# mattduino_mega_nano.net
KiCad netlist of a schematic drawn in EAGLE
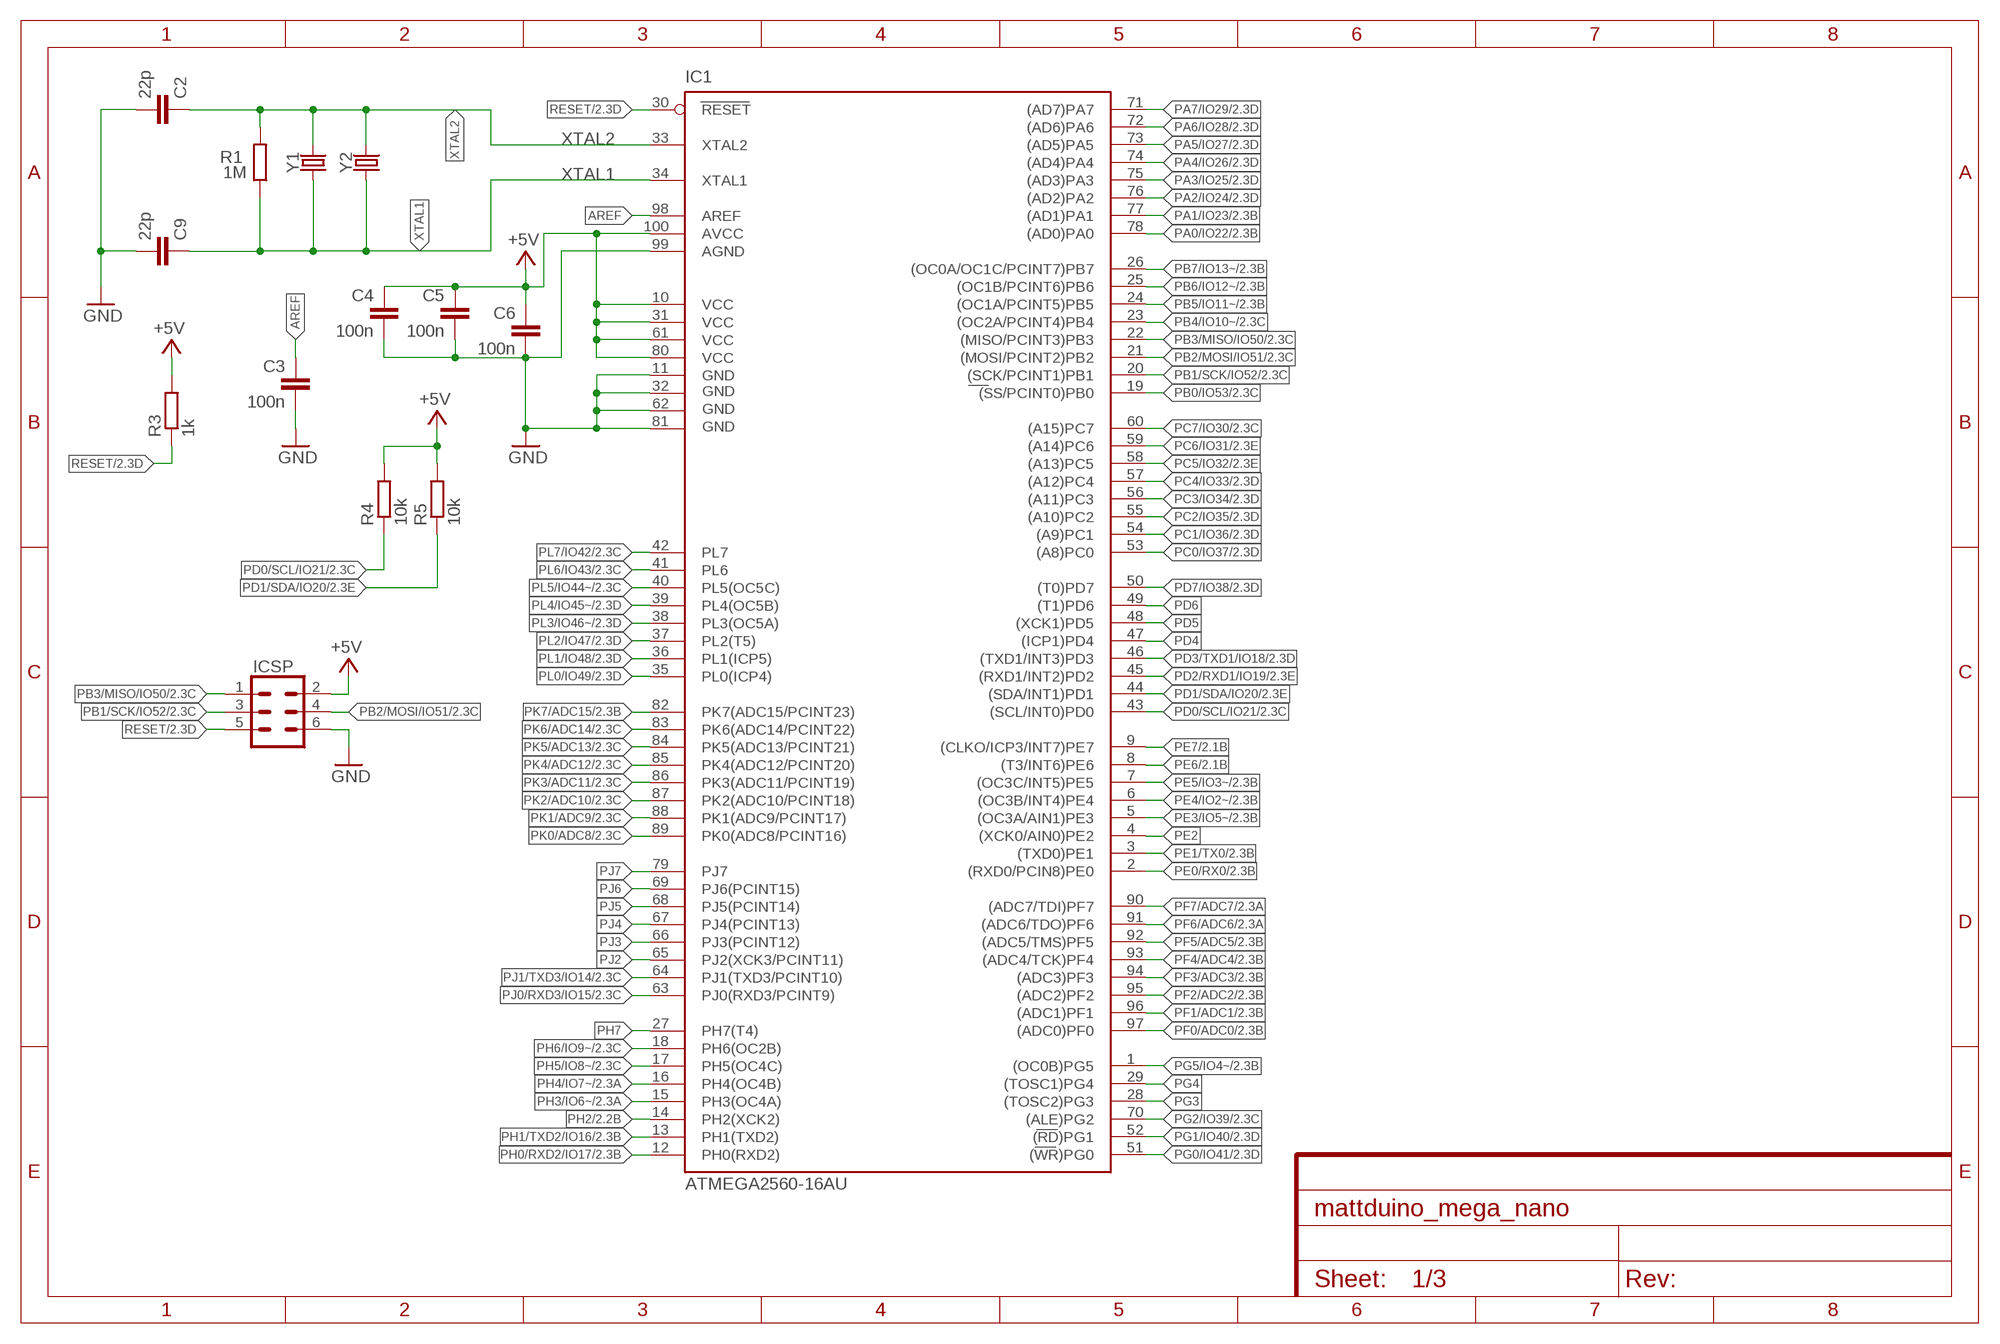
[diagram p0: schematic, sheet 1]
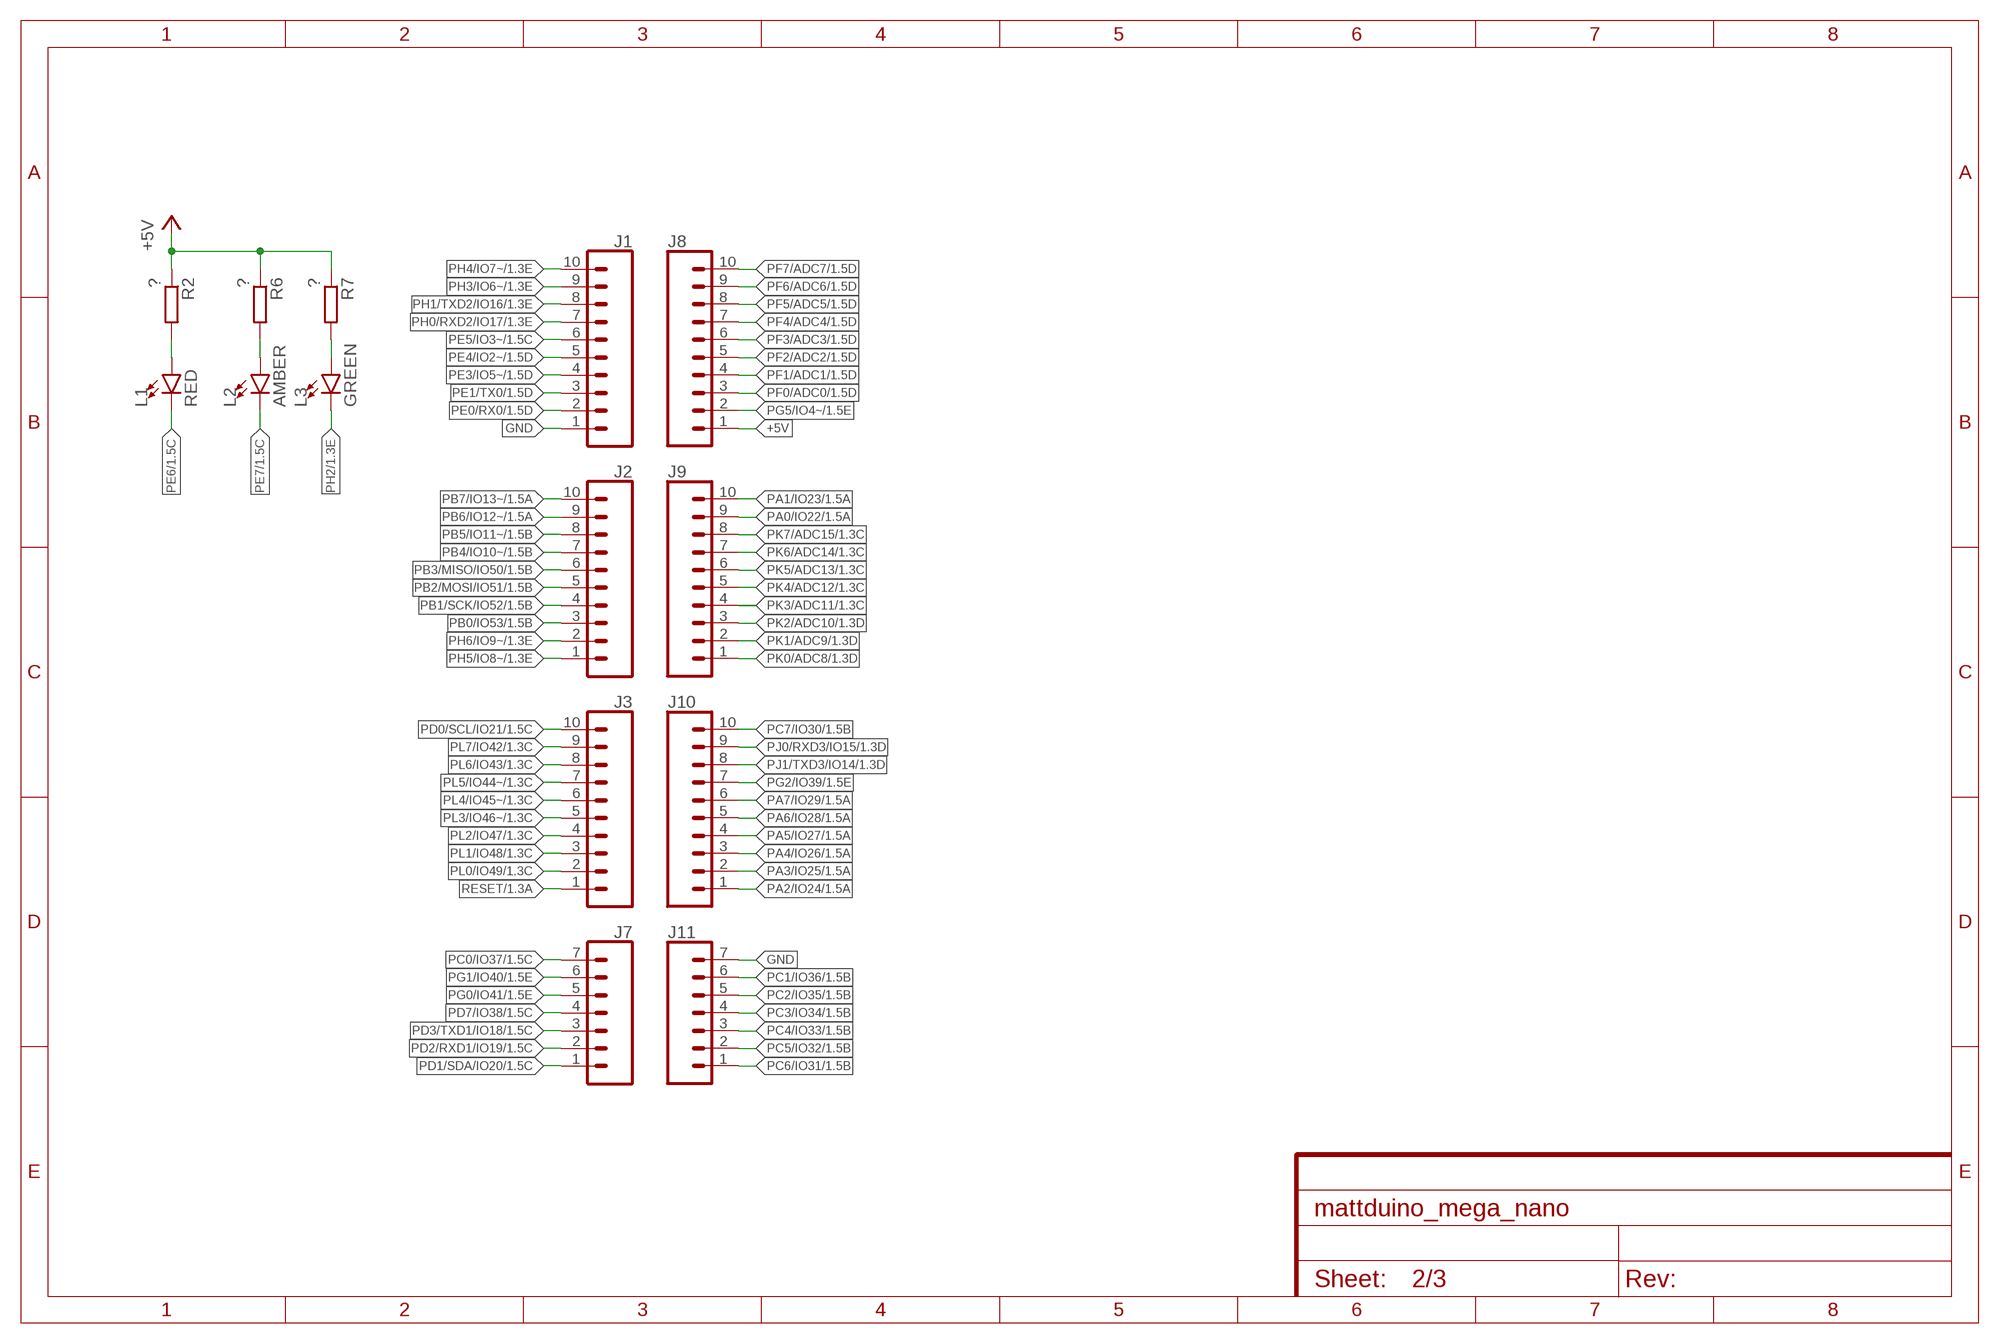
[diagram p1: schematic, sheet 2]
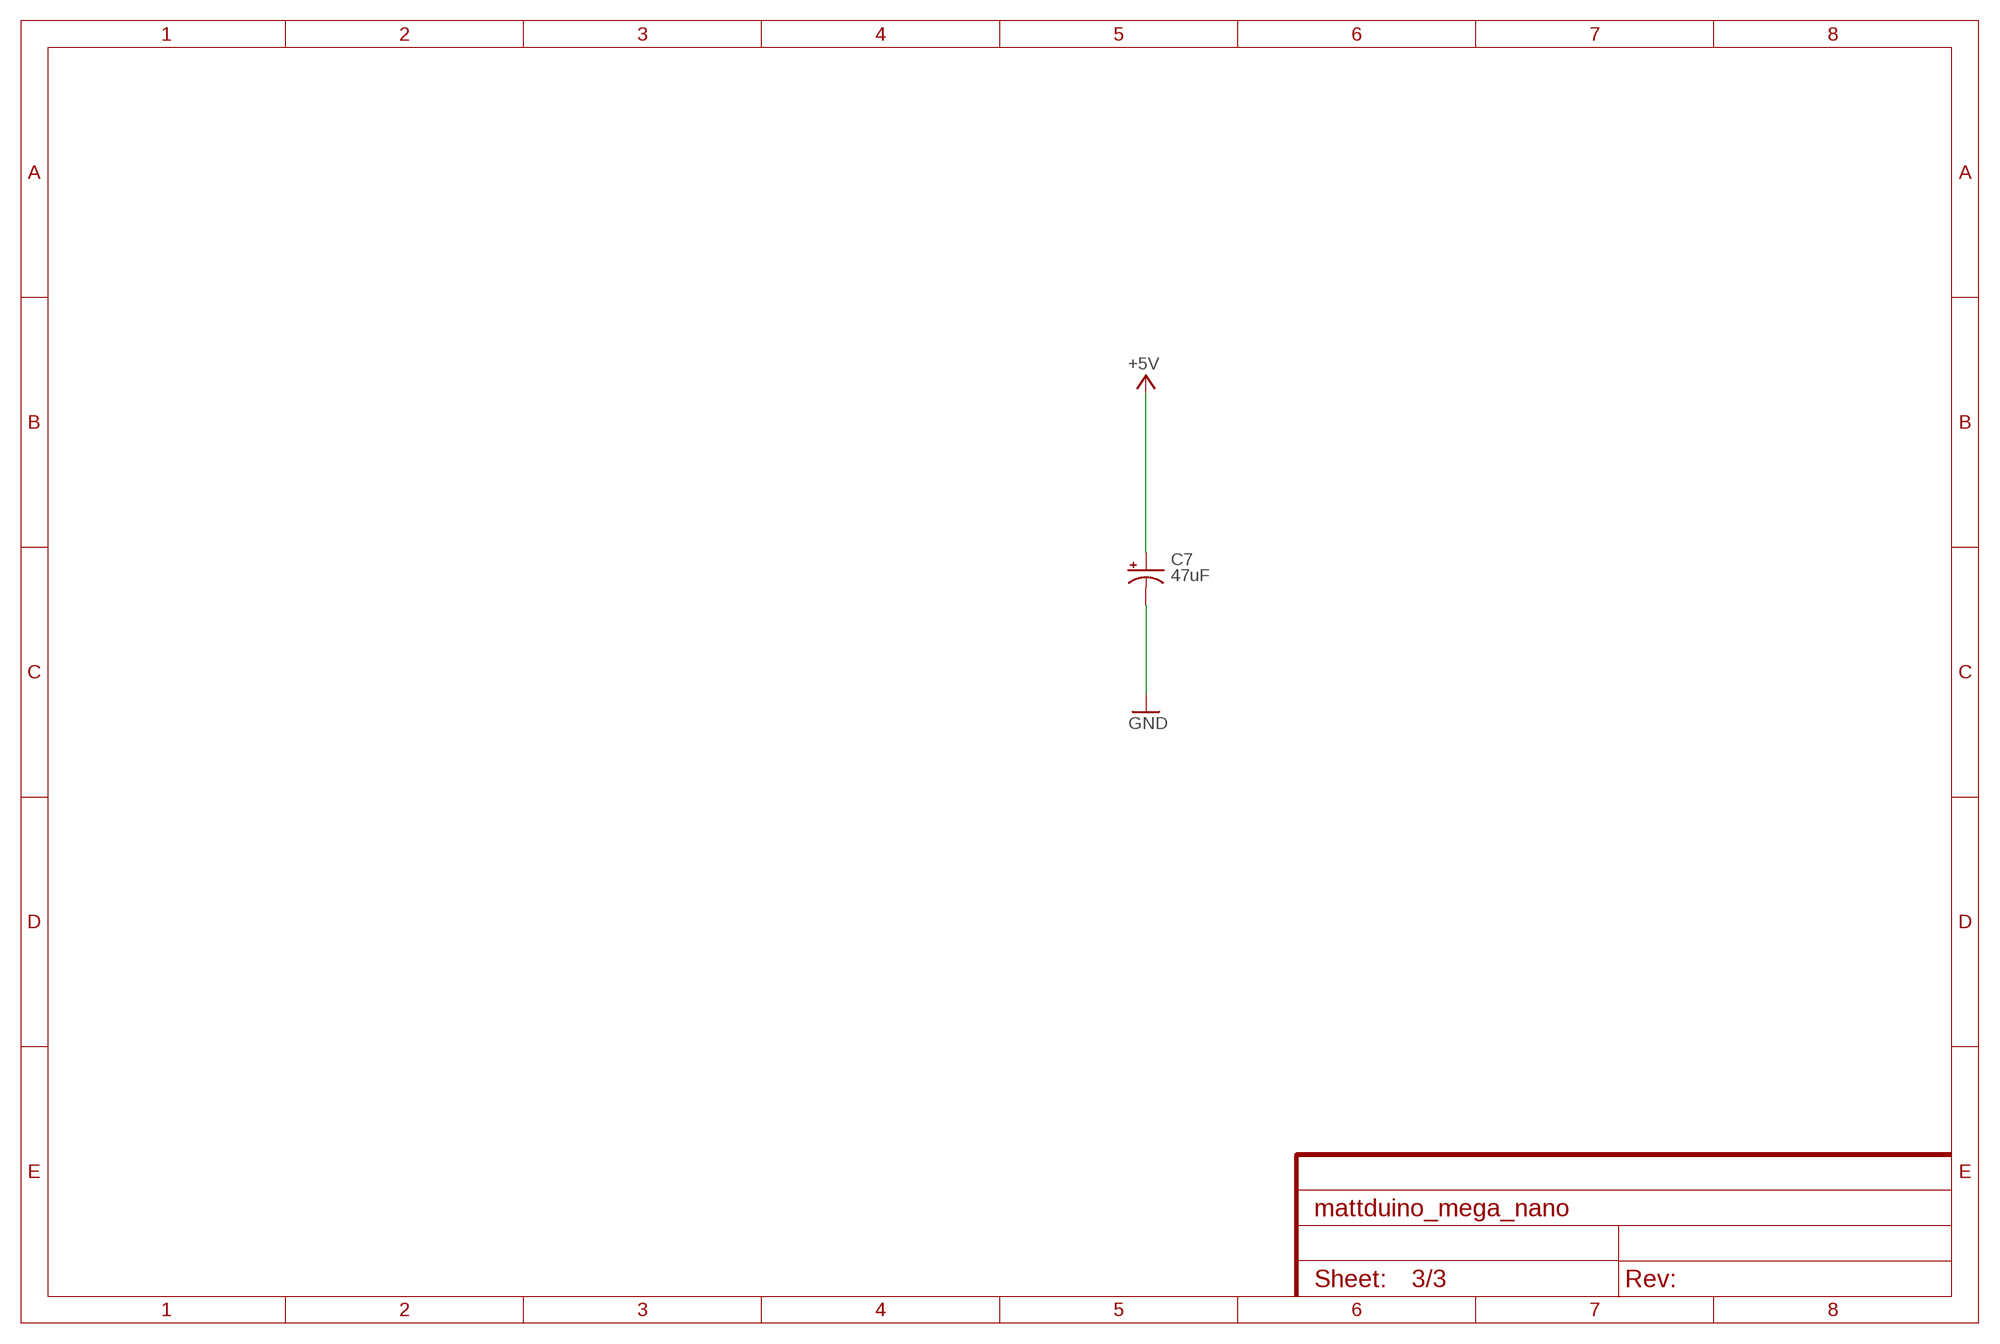
[diagram p2: schematic, sheet 3]

(export (version "E")
  (design (tool "Eeschema 10.0.6"))
  (components
    (comp (ref "J1")
      (value "CONN_10LOCK")
      (footprint "eagle-import:1X10_LOCK")
      (libsource (lib "eagle-import") (part "CONN_10LOCK"))
    )
    (comp (ref "J2")
      (value "CONN_10LOCK")
      (footprint "eagle-import:1X10_LOCK")
      (libsource (lib "eagle-import") (part "CONN_10LOCK"))
    )
    (comp (ref "J3")
      (value "CONN_10LOCK")
      (footprint "eagle-import:1X10_LOCK")
      (libsource (lib "eagle-import") (part "CONN_10LOCK"))
    )
    (comp (ref "J7")
      (value "CONN_07LOCK")
      (footprint "eagle-import:1X07_LOCK")
      (libsource (lib "eagle-import") (part "CONN_07LOCK"))
    )
    (comp (ref "J8")
      (value "CONN_10LOCK")
      (footprint "eagle-import:1X10_LOCK")
      (libsource (lib "eagle-import") (part "CONN_10LOCK"))
    )
    (comp (ref "J9")
      (value "CONN_10LOCK")
      (footprint "eagle-import:1X10_LOCK")
      (libsource (lib "eagle-import") (part "CONN_10LOCK"))
    )
    (comp (ref "J10")
      (value "CONN_10LOCK")
      (footprint "eagle-import:1X10_LOCK")
      (libsource (lib "eagle-import") (part "CONN_10LOCK"))
    )
    (comp (ref "J11")
      (value "CONN_07LOCK")
      (footprint "eagle-import:1X07_LOCK")
      (libsource (lib "eagle-import") (part "CONN_07LOCK"))
    )
    (comp (ref "L1")
      (value "RED")
      (footprint "eagle-import:LED-0603")
      (libsource (lib "eagle-import") (part "LED0603"))
    )
    (comp (ref "L2")
      (value "AMBER")
      (footprint "eagle-import:LED-0603")
      (libsource (lib "eagle-import") (part "LED0603"))
    )
    (comp (ref "L3")
      (value "GREEN")
      (footprint "eagle-import:LED-0603")
      (libsource (lib "eagle-import") (part "LED0603"))
    )
    (comp (ref "R2")
      (value "?")
      (footprint "eagle-import:R0603")
      (libsource (lib "eagle-import") (part "R-EU_R0603"))
    )
    (comp (ref "R6")
      (value "?")
      (footprint "eagle-import:R0603")
      (libsource (lib "eagle-import") (part "R-EU_R0603"))
    )
    (comp (ref "R7")
      (value "?")
      (footprint "eagle-import:R0603")
      (libsource (lib "eagle-import") (part "R-EU_R0603"))
    )
    (comp (ref "C7")
      (value "47uF")
      (footprint "eagle-import:PANASONIC_D")
      (libsource (lib "eagle-import") (part "47UF-POLAR-PANASONIC_D-35V-20%"))
    )
    (comp (ref "C2")
      (value "22p")
      (footprint "eagle-import:C0603")
      (libsource (lib "eagle-import") (part "C-EUC0603"))
    )
    (comp (ref "C3")
      (value "100n")
      (footprint "eagle-import:C0603")
      (libsource (lib "eagle-import") (part "C-EUC0603"))
    )
    (comp (ref "C4")
      (value "100n")
      (footprint "eagle-import:C0603")
      (libsource (lib "eagle-import") (part "C-EUC0603"))
    )
    (comp (ref "C5")
      (value "100n")
      (footprint "eagle-import:C0603")
      (libsource (lib "eagle-import") (part "C-EUC0603"))
    )
    (comp (ref "C6")
      (value "100n")
      (footprint "eagle-import:C0603")
      (libsource (lib "eagle-import") (part "C-EUC0603"))
    )
    (comp (ref "C9")
      (value "22p")
      (footprint "eagle-import:C0603")
      (libsource (lib "eagle-import") (part "C-EUC0603"))
    )
    (comp (ref "IC1")
      (value "ATMEGA2560-16AU")
      (footprint "eagle-import:TQFP100")
      (libsource (lib "eagle-import") (part "ATMEGA2560AU2560-16"))
    )
    (comp (ref "ICSP")
      (value "CONN_03X2SHROUD")
      (footprint "eagle-import:2X3-SHROUDED")
      (libsource (lib "eagle-import") (part "CONN_03X2SHROUD"))
    )
    (comp (ref "R1")
      (value "1M")
      (footprint "eagle-import:R0603")
      (libsource (lib "eagle-import") (part "R-EU_R0603"))
    )
    (comp (ref "R3")
      (value "1k")
      (footprint "eagle-import:R0603")
      (libsource (lib "eagle-import") (part "R-EU_R0603"))
    )
    (comp (ref "R4")
      (value "10k")
      (footprint "eagle-import:R0603")
      (libsource (lib "eagle-import") (part "R-EU_R0603"))
    )
    (comp (ref "R5")
      (value "10k")
      (footprint "eagle-import:R0603")
      (libsource (lib "eagle-import") (part "R-EU_R0603"))
    )
    (comp (ref "Y1")
      (value "CRYSTALPTH-HC49UV")
      (footprint "eagle-import:HC49U")
      (libsource (lib "eagle-import") (part "CRYSTALPTH-HC49UV"))
    )
    (comp (ref "Y2")
      (value "CRYSTALSMD-HC49UP")
      (footprint "eagle-import:HC49UP")
      (libsource (lib "eagle-import") (part "CRYSTALSMD-HC49UP"))
    )
  )
  (nets
    (net (code "1") (name "+5V") (class "Default")
      (node (ref "C4") (pin "1") (pinfunction "1_1") (pintype "passive"))
      (node (ref "C5") (pin "1") (pinfunction "1_1") (pintype "passive"))
      (node (ref "C6") (pin "1") (pinfunction "1_1") (pintype "passive"))
      (node (ref "C7") (pin "+") (pinfunction "+_+") (pintype "passive"))
      (node (ref "IC1") (pin "10") (pinfunction "VCC_10") (pintype "power_in"))
      (node (ref "IC1") (pin "100") (pinfunction "AVCC_100") (pintype "power_in"))
      (node (ref "IC1") (pin "31") (pinfunction "VCC1_31") (pintype "power_in"))
      (node (ref "IC1") (pin "61") (pinfunction "VCC2_61") (pintype "power_in"))
      (node (ref "IC1") (pin "80") (pinfunction "VCC3_80") (pintype "power_in"))
      (node (ref "ICSP") (pin "2") (pinfunction "2_2") (pintype "bidirectional"))
      (node (ref "J8") (pin "1") (pinfunction "1_1") (pintype "passive"))
      (node (ref "R2") (pin "1") (pinfunction "1_1") (pintype "passive"))
      (node (ref "R3") (pin "2") (pinfunction "2_2") (pintype "passive"))
      (node (ref "R4") (pin "2") (pinfunction "2_2") (pintype "passive"))
      (node (ref "R5") (pin "2") (pinfunction "2_2") (pintype "passive"))
      (node (ref "R6") (pin "1") (pinfunction "1_1") (pintype "passive"))
      (node (ref "R7") (pin "1") (pinfunction "1_1") (pintype "passive"))
    )
    (net (code "2") (name "AREF") (class "Default")
      (node (ref "C3") (pin "1") (pinfunction "1_1") (pintype "passive"))
      (node (ref "IC1") (pin "98") (pinfunction "AREF_98") (pintype "bidirectional"))
    )
    (net (code "3") (name "GND") (class "Default")
      (node (ref "C2") (pin "2") (pinfunction "2_2") (pintype "passive"))
      (node (ref "C3") (pin "2") (pinfunction "2_2") (pintype "passive"))
      (node (ref "C4") (pin "2") (pinfunction "2_2") (pintype "passive"))
      (node (ref "C5") (pin "2") (pinfunction "2_2") (pintype "passive"))
      (node (ref "C6") (pin "2") (pinfunction "2_2") (pintype "passive"))
      (node (ref "C7") (pin "-") (pinfunction "-_-") (pintype "passive"))
      (node (ref "C9") (pin "2") (pinfunction "2_2") (pintype "passive"))
      (node (ref "IC1") (pin "11") (pinfunction "GND_11") (pintype "power_in"))
      (node (ref "IC1") (pin "32") (pinfunction "GND1_32") (pintype "power_in"))
      (node (ref "IC1") (pin "62") (pinfunction "GND2_62") (pintype "power_in"))
      (node (ref "IC1") (pin "81") (pinfunction "GND3_81") (pintype "power_in"))
      (node (ref "IC1") (pin "99") (pinfunction "AGND_99") (pintype "power_in"))
      (node (ref "ICSP") (pin "6") (pinfunction "6_6") (pintype "bidirectional"))
      (node (ref "J1") (pin "1") (pinfunction "1_1") (pintype "passive"))
      (node (ref "J11") (pin "7") (pinfunction "7_7") (pintype "passive"))
    )
    (net (code "4") (name "Net-(L1-PadA)") (class "Default")
      (node (ref "L1") (pin "A") (pinfunction "A_A") (pintype "passive"))
      (node (ref "R2") (pin "2") (pinfunction "2_2") (pintype "passive"))
    )
    (net (code "5") (name "Net-(L2-PadA)") (class "Default")
      (node (ref "L2") (pin "A") (pinfunction "A_A") (pintype "passive"))
      (node (ref "R6") (pin "2") (pinfunction "2_2") (pintype "passive"))
    )
    (net (code "6") (name "Net-(L3-PadA)") (class "Default")
      (node (ref "L3") (pin "A") (pinfunction "A_A") (pintype "passive"))
      (node (ref "R7") (pin "2") (pinfunction "2_2") (pintype "passive"))
    )
    (net (code "7") (name "PA0{slash}IO22") (class "Default")
      (node (ref "IC1") (pin "78") (pinfunction "(AD0)PA0_78") (pintype "bidirectional"))
      (node (ref "J9") (pin "9") (pinfunction "9_9") (pintype "passive"))
    )
    (net (code "8") (name "PA1{slash}IO23") (class "Default")
      (node (ref "IC1") (pin "77") (pinfunction "(AD1)PA1_77") (pintype "bidirectional"))
      (node (ref "J9") (pin "10") (pinfunction "10_10") (pintype "passive"))
    )
    (net (code "9") (name "PA2{slash}IO24") (class "Default")
      (node (ref "IC1") (pin "76") (pinfunction "(AD2)PA2_76") (pintype "bidirectional"))
      (node (ref "J10") (pin "1") (pinfunction "1_1") (pintype "passive"))
    )
    (net (code "10") (name "PA3{slash}IO25") (class "Default")
      (node (ref "IC1") (pin "75") (pinfunction "(AD3)PA3_75") (pintype "bidirectional"))
      (node (ref "J10") (pin "2") (pinfunction "2_2") (pintype "passive"))
    )
    (net (code "11") (name "PA4{slash}IO26") (class "Default")
      (node (ref "IC1") (pin "74") (pinfunction "(AD4)PA4_74") (pintype "bidirectional"))
      (node (ref "J10") (pin "3") (pinfunction "3_3") (pintype "passive"))
    )
    (net (code "12") (name "PA5{slash}IO27") (class "Default")
      (node (ref "IC1") (pin "73") (pinfunction "(AD5)PA5_73") (pintype "bidirectional"))
      (node (ref "J10") (pin "4") (pinfunction "4_4") (pintype "passive"))
    )
    (net (code "13") (name "PA6{slash}IO28") (class "Default")
      (node (ref "IC1") (pin "72") (pinfunction "(AD6)PA6_72") (pintype "bidirectional"))
      (node (ref "J10") (pin "5") (pinfunction "5_5") (pintype "passive"))
    )
    (net (code "14") (name "PA7{slash}IO29") (class "Default")
      (node (ref "IC1") (pin "71") (pinfunction "(AD7)PA7_71") (pintype "bidirectional"))
      (node (ref "J10") (pin "6") (pinfunction "6_6") (pintype "passive"))
    )
    (net (code "15") (name "PB0{slash}IO53") (class "Default")
      (node (ref "IC1") (pin "19") (pinfunction "(SS/PCINT0)PB0_19") (pintype "bidirectional"))
      (node (ref "J2") (pin "3") (pinfunction "3_3") (pintype "passive"))
    )
    (net (code "16") (name "PB1{slash}SCK{slash}IO52") (class "Default")
      (node (ref "IC1") (pin "20") (pinfunction "(SCK/PCINT1)PB1_20") (pintype "bidirectional"))
      (node (ref "ICSP") (pin "3") (pinfunction "3_3") (pintype "bidirectional"))
      (node (ref "J2") (pin "4") (pinfunction "4_4") (pintype "passive"))
    )
    (net (code "17") (name "PB2{slash}MOSI{slash}IO51") (class "Default")
      (node (ref "IC1") (pin "21") (pinfunction "(MOSI/PCINT2)PB2_21") (pintype "bidirectional"))
      (node (ref "ICSP") (pin "4") (pinfunction "4_4") (pintype "bidirectional"))
      (node (ref "J2") (pin "5") (pinfunction "5_5") (pintype "passive"))
    )
    (net (code "18") (name "PB3{slash}MISO{slash}IO50") (class "Default")
      (node (ref "IC1") (pin "22") (pinfunction "(MISO/PCINT3)PB3_22") (pintype "bidirectional"))
      (node (ref "ICSP") (pin "1") (pinfunction "1_1") (pintype "bidirectional"))
      (node (ref "J2") (pin "6") (pinfunction "6_6") (pintype "passive"))
    )
    (net (code "19") (name "PB4{slash}IO10~{}") (class "Default")
      (node (ref "IC1") (pin "23") (pinfunction "(OC2A/PCINT4)PB4_23") (pintype "bidirectional"))
      (node (ref "J2") (pin "7") (pinfunction "7_7") (pintype "passive"))
    )
    (net (code "20") (name "PB5{slash}IO11~{}") (class "Default")
      (node (ref "IC1") (pin "24") (pinfunction "(OC1A/PCINT5)PB5_24") (pintype "bidirectional"))
      (node (ref "J2") (pin "8") (pinfunction "8_8") (pintype "passive"))
    )
    (net (code "21") (name "PB6{slash}IO12~{}") (class "Default")
      (node (ref "IC1") (pin "25") (pinfunction "(OC1B/PCINT6)PB6_25") (pintype "bidirectional"))
      (node (ref "J2") (pin "9") (pinfunction "9_9") (pintype "passive"))
    )
    (net (code "22") (name "PB7{slash}IO13~{}") (class "Default")
      (node (ref "IC1") (pin "26") (pinfunction "(OC0A/OC1C/PCINT7)PB7_26") (pintype "bidirectional"))
      (node (ref "J2") (pin "10") (pinfunction "10_10") (pintype "passive"))
    )
    (net (code "23") (name "PC0{slash}IO37") (class "Default")
      (node (ref "IC1") (pin "53") (pinfunction "(A8)PC0_53") (pintype "bidirectional"))
      (node (ref "J7") (pin "7") (pinfunction "7_7") (pintype "passive"))
    )
    (net (code "24") (name "PC1{slash}IO36") (class "Default")
      (node (ref "IC1") (pin "54") (pinfunction "(A9)PC1_54") (pintype "bidirectional"))
      (node (ref "J11") (pin "6") (pinfunction "6_6") (pintype "passive"))
    )
    (net (code "25") (name "PC2{slash}IO35") (class "Default")
      (node (ref "IC1") (pin "55") (pinfunction "(A10)PC2_55") (pintype "bidirectional"))
      (node (ref "J11") (pin "5") (pinfunction "5_5") (pintype "passive"))
    )
    (net (code "26") (name "PC3{slash}IO34") (class "Default")
      (node (ref "IC1") (pin "56") (pinfunction "(A11)PC3_56") (pintype "bidirectional"))
      (node (ref "J11") (pin "4") (pinfunction "4_4") (pintype "passive"))
    )
    (net (code "27") (name "PC4{slash}IO33") (class "Default")
      (node (ref "IC1") (pin "57") (pinfunction "(A12)PC4_57") (pintype "bidirectional"))
      (node (ref "J11") (pin "3") (pinfunction "3_3") (pintype "passive"))
    )
    (net (code "28") (name "PC5{slash}IO32") (class "Default")
      (node (ref "IC1") (pin "58") (pinfunction "(A13)PC5_58") (pintype "bidirectional"))
      (node (ref "J11") (pin "2") (pinfunction "2_2") (pintype "passive"))
    )
    (net (code "29") (name "PC6{slash}IO31") (class "Default")
      (node (ref "IC1") (pin "59") (pinfunction "(A14)PC6_59") (pintype "bidirectional"))
      (node (ref "J11") (pin "1") (pinfunction "1_1") (pintype "passive"))
    )
    (net (code "30") (name "PC7{slash}IO30") (class "Default")
      (node (ref "IC1") (pin "60") (pinfunction "(A15)PC7_60") (pintype "bidirectional"))
      (node (ref "J10") (pin "10") (pinfunction "10_10") (pintype "passive"))
    )
    (net (code "31") (name "PD0{slash}SCL{slash}IO21") (class "Default")
      (node (ref "IC1") (pin "43") (pinfunction "(SCL/INT0)PD0_43") (pintype "bidirectional"))
      (node (ref "J3") (pin "10") (pinfunction "10_10") (pintype "passive"))
      (node (ref "R4") (pin "1") (pinfunction "1_1") (pintype "passive"))
    )
    (net (code "32") (name "PD1{slash}SDA{slash}IO20") (class "Default")
      (node (ref "IC1") (pin "44") (pinfunction "(SDA/INT1)PD1_44") (pintype "bidirectional"))
      (node (ref "J7") (pin "1") (pinfunction "1_1") (pintype "passive"))
      (node (ref "R5") (pin "1") (pinfunction "1_1") (pintype "passive"))
    )
    (net (code "33") (name "PD2{slash}RXD1{slash}IO19") (class "Default")
      (node (ref "IC1") (pin "45") (pinfunction "(RXD1/INT2)PD2_45") (pintype "bidirectional"))
      (node (ref "J7") (pin "2") (pinfunction "2_2") (pintype "passive"))
    )
    (net (code "34") (name "PD3{slash}TXD1{slash}IO18") (class "Default")
      (node (ref "IC1") (pin "46") (pinfunction "(TXD1/INT3)PD3_46") (pintype "bidirectional"))
      (node (ref "J7") (pin "3") (pinfunction "3_3") (pintype "passive"))
    )
    (net (code "35") (name "PD4") (class "Default")
      (node (ref "IC1") (pin "47") (pinfunction "(ICP1)PD4_47") (pintype "bidirectional"))
    )
    (net (code "36") (name "PD5") (class "Default")
      (node (ref "IC1") (pin "48") (pinfunction "(XCK1)PD5_48") (pintype "bidirectional"))
    )
    (net (code "37") (name "PD6") (class "Default")
      (node (ref "IC1") (pin "49") (pinfunction "(T1)PD6_49") (pintype "bidirectional"))
    )
    (net (code "38") (name "PD7{slash}IO38") (class "Default")
      (node (ref "IC1") (pin "50") (pinfunction "(T0)PD7_50") (pintype "bidirectional"))
      (node (ref "J7") (pin "4") (pinfunction "4_4") (pintype "passive"))
    )
    (net (code "39") (name "PE0{slash}RX0") (class "Default")
      (node (ref "IC1") (pin "2") (pinfunction "(RXD0/PCIN8)PE0_2") (pintype "bidirectional"))
      (node (ref "J1") (pin "2") (pinfunction "2_2") (pintype "passive"))
    )
    (net (code "40") (name "PE1{slash}TX0") (class "Default")
      (node (ref "IC1") (pin "3") (pinfunction "(TXD0)PE1_3") (pintype "bidirectional"))
      (node (ref "J1") (pin "3") (pinfunction "3_3") (pintype "passive"))
    )
    (net (code "41") (name "PE2") (class "Default")
      (node (ref "IC1") (pin "4") (pinfunction "(XCK0/AIN0)PE2_4") (pintype "bidirectional"))
    )
    (net (code "42") (name "PE3{slash}IO5~{}") (class "Default")
      (node (ref "IC1") (pin "5") (pinfunction "(OC3A/AIN1)PE3_5") (pintype "bidirectional"))
      (node (ref "J1") (pin "4") (pinfunction "4_4") (pintype "passive"))
    )
    (net (code "43") (name "PE4{slash}IO2~{}") (class "Default")
      (node (ref "IC1") (pin "6") (pinfunction "(OC3B/INT4)PE4_6") (pintype "bidirectional"))
      (node (ref "J1") (pin "5") (pinfunction "5_5") (pintype "passive"))
    )
    (net (code "44") (name "PE5{slash}IO3~{}") (class "Default")
      (node (ref "IC1") (pin "7") (pinfunction "(OC3C/INT5)PE5_7") (pintype "bidirectional"))
      (node (ref "J1") (pin "6") (pinfunction "6_6") (pintype "passive"))
    )
    (net (code "45") (name "PE6") (class "Default")
      (node (ref "IC1") (pin "8") (pinfunction "(T3/INT6)PE6_8") (pintype "bidirectional"))
      (node (ref "L1") (pin "C") (pinfunction "C_C") (pintype "passive"))
    )
    (net (code "46") (name "PE7") (class "Default")
      (node (ref "IC1") (pin "9") (pinfunction "(CLKO/ICP3/INT7)PE7_9") (pintype "bidirectional"))
      (node (ref "L2") (pin "C") (pinfunction "C_C") (pintype "passive"))
    )
    (net (code "47") (name "PF0{slash}ADC0") (class "Default")
      (node (ref "IC1") (pin "97") (pinfunction "(ADC0)PF0_97") (pintype "bidirectional"))
      (node (ref "J8") (pin "3") (pinfunction "3_3") (pintype "passive"))
    )
    (net (code "48") (name "PF1{slash}ADC1") (class "Default")
      (node (ref "IC1") (pin "96") (pinfunction "(ADC1)PF1_96") (pintype "bidirectional"))
      (node (ref "J8") (pin "4") (pinfunction "4_4") (pintype "passive"))
    )
    (net (code "49") (name "PF2{slash}ADC2") (class "Default")
      (node (ref "IC1") (pin "95") (pinfunction "(ADC2)PF2_95") (pintype "bidirectional"))
      (node (ref "J8") (pin "5") (pinfunction "5_5") (pintype "passive"))
    )
    (net (code "50") (name "PF3{slash}ADC3") (class "Default")
      (node (ref "IC1") (pin "94") (pinfunction "(ADC3)PF3_94") (pintype "bidirectional"))
      (node (ref "J8") (pin "6") (pinfunction "6_6") (pintype "passive"))
    )
    (net (code "51") (name "PF4{slash}ADC4") (class "Default")
      (node (ref "IC1") (pin "93") (pinfunction "(ADC4/TCK)PF4_93") (pintype "bidirectional"))
      (node (ref "J8") (pin "7") (pinfunction "7_7") (pintype "passive"))
    )
    (net (code "52") (name "PF5{slash}ADC5") (class "Default")
      (node (ref "IC1") (pin "92") (pinfunction "(ADC5/TMS)PF5_92") (pintype "bidirectional"))
      (node (ref "J8") (pin "8") (pinfunction "8_8") (pintype "passive"))
    )
    (net (code "53") (name "PF6{slash}ADC6") (class "Default")
      (node (ref "IC1") (pin "91") (pinfunction "(ADC6/TDO)PF6_91") (pintype "bidirectional"))
      (node (ref "J8") (pin "9") (pinfunction "9_9") (pintype "passive"))
    )
    (net (code "54") (name "PF7{slash}ADC7") (class "Default")
      (node (ref "IC1") (pin "90") (pinfunction "(ADC7/TDI)PF7_90") (pintype "bidirectional"))
      (node (ref "J8") (pin "10") (pinfunction "10_10") (pintype "passive"))
    )
    (net (code "55") (name "PG0{slash}IO41") (class "Default")
      (node (ref "IC1") (pin "51") (pinfunction "(WR)PG0_51") (pintype "bidirectional"))
      (node (ref "J7") (pin "5") (pinfunction "5_5") (pintype "passive"))
    )
    (net (code "56") (name "PG1{slash}IO40") (class "Default")
      (node (ref "IC1") (pin "52") (pinfunction "(RD)PG1_52") (pintype "bidirectional"))
      (node (ref "J7") (pin "6") (pinfunction "6_6") (pintype "passive"))
    )
    (net (code "57") (name "PG2{slash}IO39") (class "Default")
      (node (ref "IC1") (pin "70") (pinfunction "(ALE)PG2_70") (pintype "bidirectional"))
      (node (ref "J10") (pin "7") (pinfunction "7_7") (pintype "passive"))
    )
    (net (code "58") (name "PG3") (class "Default")
      (node (ref "IC1") (pin "28") (pinfunction "(TOSC2)PG3_28") (pintype "bidirectional"))
    )
    (net (code "59") (name "PG4") (class "Default")
      (node (ref "IC1") (pin "29") (pinfunction "(TOSC1)PG4_29") (pintype "bidirectional"))
    )
    (net (code "60") (name "PG5{slash}IO4~{}") (class "Default")
      (node (ref "IC1") (pin "1") (pinfunction "(OC0B)PG5_1") (pintype "bidirectional"))
      (node (ref "J8") (pin "2") (pinfunction "2_2") (pintype "passive"))
    )
    (net (code "61") (name "PH0{slash}RXD2{slash}IO17") (class "Default")
      (node (ref "IC1") (pin "12") (pinfunction "PH0(RXD2)_12") (pintype "bidirectional"))
      (node (ref "J1") (pin "7") (pinfunction "7_7") (pintype "passive"))
    )
    (net (code "62") (name "PH1{slash}TXD2{slash}IO16") (class "Default")
      (node (ref "IC1") (pin "13") (pinfunction "PH1(TXD2)_13") (pintype "bidirectional"))
      (node (ref "J1") (pin "8") (pinfunction "8_8") (pintype "passive"))
    )
    (net (code "63") (name "PH2") (class "Default")
      (node (ref "IC1") (pin "14") (pinfunction "PH2(XCK2)_14") (pintype "bidirectional"))
      (node (ref "L3") (pin "C") (pinfunction "C_C") (pintype "passive"))
    )
    (net (code "64") (name "PH3{slash}IO6~{}") (class "Default")
      (node (ref "IC1") (pin "15") (pinfunction "PH3(OC4A)_15") (pintype "bidirectional"))
      (node (ref "J1") (pin "9") (pinfunction "9_9") (pintype "passive"))
    )
    (net (code "65") (name "PH4{slash}IO7~{}") (class "Default")
      (node (ref "IC1") (pin "16") (pinfunction "PH4(OC4B)_16") (pintype "bidirectional"))
      (node (ref "J1") (pin "10") (pinfunction "10_10") (pintype "passive"))
    )
    (net (code "66") (name "PH5{slash}IO8~{}") (class "Default")
      (node (ref "IC1") (pin "17") (pinfunction "PH5(OC4C)_17") (pintype "bidirectional"))
      (node (ref "J2") (pin "1") (pinfunction "1_1") (pintype "passive"))
    )
    (net (code "67") (name "PH6{slash}IO9~{}") (class "Default")
      (node (ref "IC1") (pin "18") (pinfunction "PH6(OC2B)_18") (pintype "bidirectional"))
      (node (ref "J2") (pin "2") (pinfunction "2_2") (pintype "passive"))
    )
    (net (code "68") (name "PH7") (class "Default")
      (node (ref "IC1") (pin "27") (pinfunction "PH7(T4)_27") (pintype "bidirectional"))
    )
    (net (code "69") (name "PJ0{slash}RXD3{slash}IO15") (class "Default")
      (node (ref "IC1") (pin "63") (pinfunction "PJ0(RXD3/PCINT9)_63") (pintype "bidirectional"))
      (node (ref "J10") (pin "9") (pinfunction "9_9") (pintype "passive"))
    )
    (net (code "70") (name "PJ1{slash}TXD3{slash}IO14") (class "Default")
      (node (ref "IC1") (pin "64") (pinfunction "PJ1(TXD3/PCINT10)_64") (pintype "bidirectional"))
      (node (ref "J10") (pin "8") (pinfunction "8_8") (pintype "passive"))
    )
    (net (code "71") (name "PJ2") (class "Default")
      (node (ref "IC1") (pin "65") (pinfunction "PJ2(XCK3/PCINT11)_65") (pintype "bidirectional"))
    )
    (net (code "72") (name "PJ3") (class "Default")
      (node (ref "IC1") (pin "66") (pinfunction "PJ3(PCINT12)_66") (pintype "bidirectional"))
    )
    (net (code "73") (name "PJ4") (class "Default")
      (node (ref "IC1") (pin "67") (pinfunction "PJ4(PCINT13)_67") (pintype "bidirectional"))
    )
    (net (code "74") (name "PJ5") (class "Default")
      (node (ref "IC1") (pin "68") (pinfunction "PJ5(PCINT14)_68") (pintype "bidirectional"))
    )
    (net (code "75") (name "PJ6") (class "Default")
      (node (ref "IC1") (pin "69") (pinfunction "PJ6(PCINT15)_69") (pintype "bidirectional"))
    )
    (net (code "76") (name "PJ7") (class "Default")
      (node (ref "IC1") (pin "79") (pinfunction "PJ7_79") (pintype "bidirectional"))
    )
    (net (code "77") (name "PK0{slash}ADC8") (class "Default")
      (node (ref "IC1") (pin "89") (pinfunction "PK0(ADC8/PCINT16)_89") (pintype "bidirectional"))
      (node (ref "J9") (pin "1") (pinfunction "1_1") (pintype "passive"))
    )
    (net (code "78") (name "PK1{slash}ADC9") (class "Default")
      (node (ref "IC1") (pin "88") (pinfunction "PK1(ADC9/PCINT17)_88") (pintype "bidirectional"))
      (node (ref "J9") (pin "2") (pinfunction "2_2") (pintype "passive"))
    )
    (net (code "79") (name "PK2{slash}ADC10") (class "Default")
      (node (ref "IC1") (pin "87") (pinfunction "PK2(ADC10/PCINT18)_87") (pintype "bidirectional"))
      (node (ref "J9") (pin "3") (pinfunction "3_3") (pintype "passive"))
    )
    (net (code "80") (name "PK3{slash}ADC11") (class "Default")
      (node (ref "IC1") (pin "86") (pinfunction "PK3(ADC11/PCINT19)_86") (pintype "bidirectional"))
      (node (ref "J9") (pin "4") (pinfunction "4_4") (pintype "passive"))
    )
    (net (code "81") (name "PK4{slash}ADC12") (class "Default")
      (node (ref "IC1") (pin "85") (pinfunction "PK4(ADC12/PCINT20)_85") (pintype "bidirectional"))
      (node (ref "J9") (pin "5") (pinfunction "5_5") (pintype "passive"))
    )
    (net (code "82") (name "PK5{slash}ADC13") (class "Default")
      (node (ref "IC1") (pin "84") (pinfunction "PK5(ADC13/PCINT21)_84") (pintype "bidirectional"))
      (node (ref "J9") (pin "6") (pinfunction "6_6") (pintype "passive"))
    )
    (net (code "83") (name "PK6{slash}ADC14") (class "Default")
      (node (ref "IC1") (pin "83") (pinfunction "PK6(ADC14/PCINT22)_83") (pintype "bidirectional"))
      (node (ref "J9") (pin "7") (pinfunction "7_7") (pintype "passive"))
    )
    (net (code "84") (name "PK7{slash}ADC15") (class "Default")
      (node (ref "IC1") (pin "82") (pinfunction "PK7(ADC15/PCINT23)_82") (pintype "bidirectional"))
      (node (ref "J9") (pin "8") (pinfunction "8_8") (pintype "passive"))
    )
    (net (code "85") (name "PL0{slash}IO49") (class "Default")
      (node (ref "IC1") (pin "35") (pinfunction "PL0(ICP4)_35") (pintype "bidirectional"))
      (node (ref "J3") (pin "2") (pinfunction "2_2") (pintype "passive"))
    )
    (net (code "86") (name "PL1{slash}IO48") (class "Default")
      (node (ref "IC1") (pin "36") (pinfunction "PL1(ICP5)_36") (pintype "bidirectional"))
      (node (ref "J3") (pin "3") (pinfunction "3_3") (pintype "passive"))
    )
    (net (code "87") (name "PL2{slash}IO47") (class "Default")
      (node (ref "IC1") (pin "37") (pinfunction "PL2(T5)_37") (pintype "bidirectional"))
      (node (ref "J3") (pin "4") (pinfunction "4_4") (pintype "passive"))
    )
    (net (code "88") (name "PL3{slash}IO46~{}") (class "Default")
      (node (ref "IC1") (pin "38") (pinfunction "PL3(OC5A)_38") (pintype "bidirectional"))
      (node (ref "J3") (pin "5") (pinfunction "5_5") (pintype "passive"))
    )
    (net (code "89") (name "PL4{slash}IO45~{}") (class "Default")
      (node (ref "IC1") (pin "39") (pinfunction "PL4(OC5B)_39") (pintype "bidirectional"))
      (node (ref "J3") (pin "6") (pinfunction "6_6") (pintype "passive"))
    )
    (net (code "90") (name "PL5{slash}IO44~{}") (class "Default")
      (node (ref "IC1") (pin "40") (pinfunction "PL5(OC5C)_40") (pintype "bidirectional"))
      (node (ref "J3") (pin "7") (pinfunction "7_7") (pintype "passive"))
    )
    (net (code "91") (name "PL6{slash}IO43") (class "Default")
      (node (ref "IC1") (pin "41") (pinfunction "PL6_41") (pintype "bidirectional"))
      (node (ref "J3") (pin "8") (pinfunction "8_8") (pintype "passive"))
    )
    (net (code "92") (name "PL7{slash}IO42") (class "Default")
      (node (ref "IC1") (pin "42") (pinfunction "PL7_42") (pintype "bidirectional"))
      (node (ref "J3") (pin "9") (pinfunction "9_9") (pintype "passive"))
    )
    (net (code "93") (name "RESET") (class "Default")
      (node (ref "IC1") (pin "30") (pinfunction "RESET_30") (pintype "input"))
      (node (ref "ICSP") (pin "5") (pinfunction "5_5") (pintype "bidirectional"))
      (node (ref "J3") (pin "1") (pinfunction "1_1") (pintype "passive"))
      (node (ref "R3") (pin "1") (pinfunction "1_1") (pintype "passive"))
    )
    (net (code "94") (name "XTAL1") (class "Default")
      (node (ref "C9") (pin "1") (pinfunction "1_1") (pintype "passive"))
      (node (ref "IC1") (pin "34") (pinfunction "XTAL1_34") (pintype "input"))
      (node (ref "R1") (pin "1") (pinfunction "1_1") (pintype "passive"))
      (node (ref "Y1") (pin "1") (pinfunction "1_1") (pintype "passive"))
      (node (ref "Y2") (pin "1") (pinfunction "1_1") (pintype "passive"))
    )
    (net (code "95") (name "XTAL2") (class "Default")
      (node (ref "C2") (pin "1") (pinfunction "1_1") (pintype "passive"))
      (node (ref "IC1") (pin "33") (pinfunction "XTAL2_33") (pintype "output"))
      (node (ref "R1") (pin "2") (pinfunction "2_2") (pintype "passive"))
      (node (ref "Y1") (pin "2") (pinfunction "2_2") (pintype "passive"))
      (node (ref "Y2") (pin "2") (pinfunction "2_2") (pintype "passive"))
    )
  )
)
